# DE-130817_01.net
KiCad netlist of a schematic drawn in Altium Designer
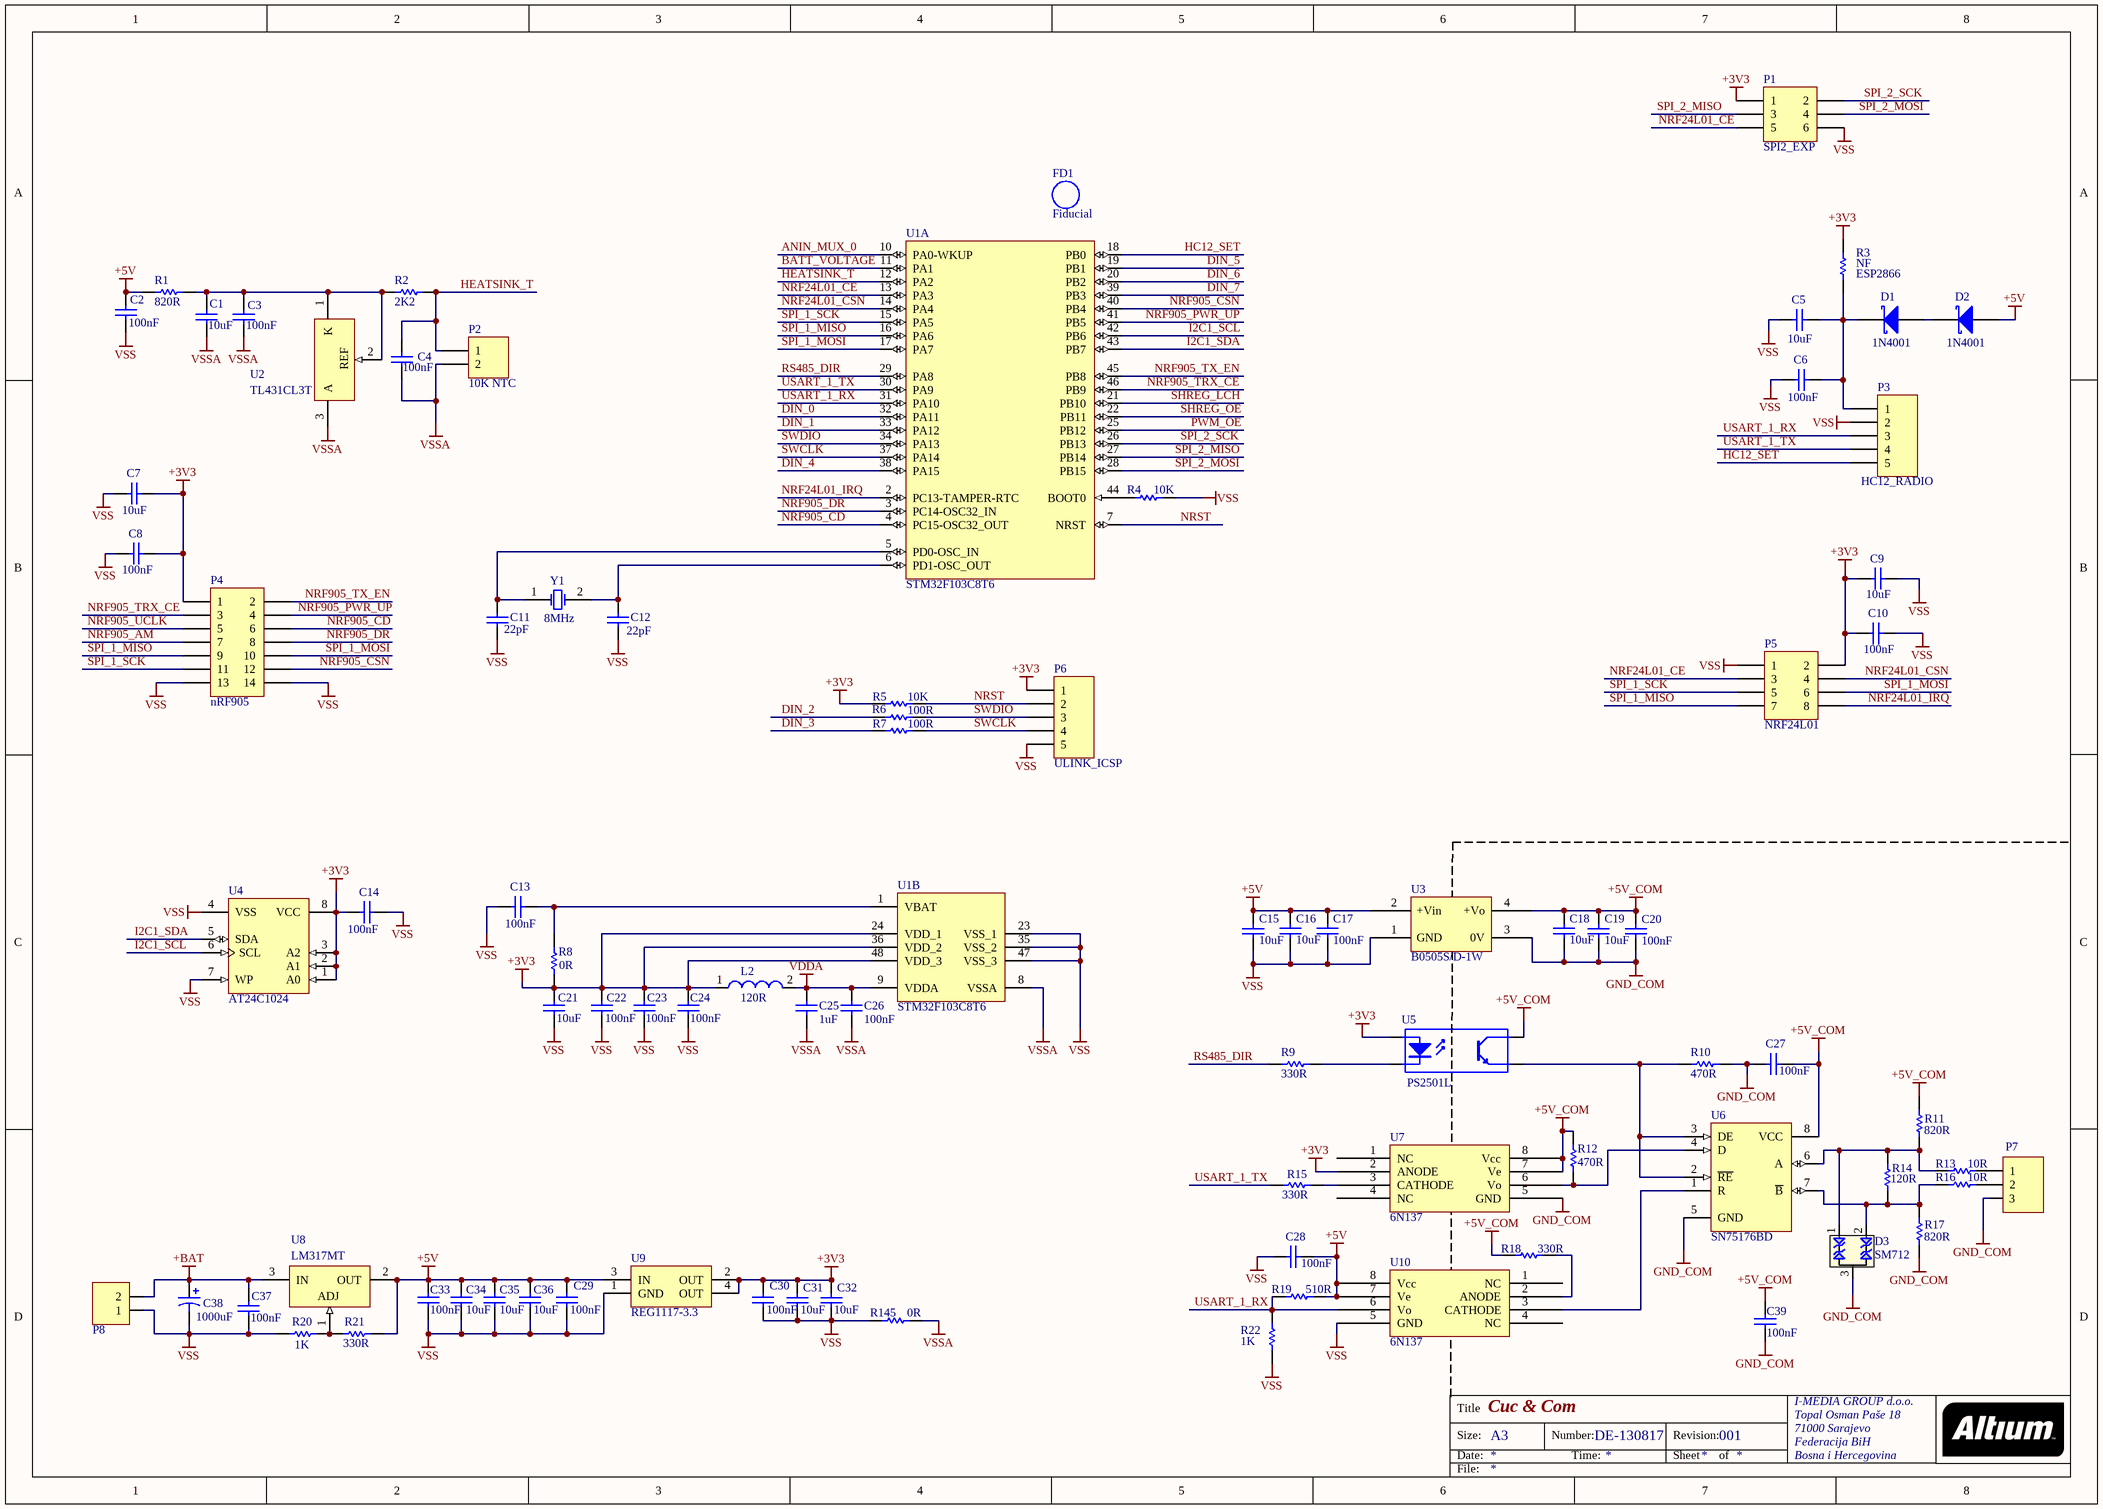
[diagram p0: DE-130817_01.SchDoc]

(export (version "E")
  (design (tool "Eeschema 10.0.6"))
  (components
    (comp (ref "C1")
      (value "10uF")
      (footprint "0805")
      (description "Ceramic Chip Capacitor - Standard")
      (fields (field (name "PUBLISHER") "Altium Limited"))
      (libsource (lib "KEMET Chip Capacitor") (part "C0805"))
    )
    (comp (ref "C2")
      (value "100nF")
      (footprint "0603")
      (description "Ceramic Chip Capacitor - Standard")
      (fields (field (name "PUBLISHER") "Altium Limited"))
      (libsource (lib "KEMET Chip Capacitor") (part "C0603"))
    )
    (comp (ref "C3")
      (value "100nF")
      (footprint "0603")
      (description "Ceramic Chip Capacitor - Standard")
      (fields (field (name "PUBLISHER") "Altium Limited"))
      (libsource (lib "KEMET Chip Capacitor") (part "C0603"))
    )
    (comp (ref "C4")
      (value "100nF")
      (footprint "0603")
      (description "Ceramic Chip Capacitor - Standard")
      (fields (field (name "PUBLISHER") "Altium Limited"))
      (libsource (lib "KEMET Chip Capacitor") (part "C0603"))
    )
    (comp (ref "C5")
      (value "10uF")
      (footprint "0805")
      (description "Ceramic Chip Capacitor - Standard")
      (fields (field (name "PUBLISHER") "Altium Limited"))
      (libsource (lib "KEMET Chip Capacitor") (part "C0805"))
    )
    (comp (ref "C6")
      (value "100nF")
      (footprint "0603")
      (description "Ceramic Chip Capacitor - Standard")
      (fields (field (name "PUBLISHER") "Altium Limited"))
      (libsource (lib "KEMET Chip Capacitor") (part "C0603"))
    )
    (comp (ref "C7")
      (value "10uF")
      (footprint "0805")
      (description "Ceramic Chip Capacitor - Standard")
      (fields (field (name "PUBLISHER") "Altium Limited"))
      (libsource (lib "KEMET Chip Capacitor") (part "C0805"))
    )
    (comp (ref "C8")
      (value "100nF")
      (footprint "0603")
      (description "Ceramic Chip Capacitor - Standard")
      (fields (field (name "PUBLISHER") "Altium Limited"))
      (libsource (lib "KEMET Chip Capacitor") (part "C0603"))
    )
    (comp (ref "C9")
      (value "10uF")
      (footprint "0805")
      (description "Ceramic Chip Capacitor - Standard")
      (fields (field (name "PUBLISHER") "Altium Limited"))
      (libsource (lib "KEMET Chip Capacitor") (part "C0805"))
    )
    (comp (ref "C10")
      (value "100nF")
      (footprint "0603")
      (description "Ceramic Chip Capacitor - Standard")
      (fields (field (name "PUBLISHER") "Altium Limited"))
      (libsource (lib "KEMET Chip Capacitor") (part "C0603"))
    )
    (comp (ref "C11")
      (value "22pF")
      (footprint "0603")
      (description "Ceramic Chip Capacitor - Standard")
      (fields (field (name "PUBLISHER") "Altium Limited"))
      (libsource (lib "KEMET Chip Capacitor") (part "C0603"))
    )
    (comp (ref "C12")
      (value "22pF")
      (footprint "0603")
      (description "Ceramic Chip Capacitor - Standard")
      (fields (field (name "PUBLISHER") "Altium Limited"))
      (libsource (lib "KEMET Chip Capacitor") (part "C0603"))
    )
    (comp (ref "C13")
      (value "100nF")
      (footprint "0603")
      (description "Ceramic Chip Capacitor - Standard")
      (fields (field (name "PUBLISHER") "Altium Limited"))
      (libsource (lib "KEMET Chip Capacitor") (part "C0603"))
    )
    (comp (ref "C14")
      (value "100nF")
      (footprint "0603")
      (description "Ceramic Chip Capacitor - Standard")
      (fields (field (name "PUBLISHER") "Altium Limited"))
      (libsource (lib "DE-251215") (part "C0603"))
    )
    (comp (ref "C15")
      (value "10uF")
      (footprint "0805")
      (description "Ceramic Chip Capacitor - Standard")
      (fields (field (name "PUBLISHER") "Altium Limited"))
      (libsource (lib "DE-110817") (part "C0805"))
    )
    (comp (ref "C16")
      (value "10uF")
      (footprint "0805")
      (description "Ceramic Chip Capacitor - Standard")
      (fields (field (name "PUBLISHER") "Altium Limited"))
      (libsource (lib "DE-110817") (part "C0805"))
    )
    (comp (ref "C17")
      (value "100nF")
      (footprint "0603")
      (description "Ceramic Chip Capacitor - Standard")
      (fields (field (name "PUBLISHER") "Altium Limited"))
      (libsource (lib "DE-110817") (part "C0603"))
    )
    (comp (ref "C18")
      (value "10uF")
      (footprint "0805")
      (description "Ceramic Chip Capacitor - Standard")
      (fields (field (name "PUBLISHER") "Altium Limited"))
      (libsource (lib "DE-110817") (part "C0805"))
    )
    (comp (ref "C19")
      (value "10uF")
      (footprint "0805")
      (description "Ceramic Chip Capacitor - Standard")
      (fields (field (name "PUBLISHER") "Altium Limited"))
      (libsource (lib "DE-110817") (part "C0805"))
    )
    (comp (ref "C20")
      (value "100nF")
      (footprint "0603")
      (description "Ceramic Chip Capacitor - Standard")
      (fields (field (name "PUBLISHER") "Altium Limited"))
      (libsource (lib "DE-110817") (part "C0603"))
    )
    (comp (ref "C21")
      (value "10uF")
      (footprint "0805")
      (description "Ceramic Chip Capacitor - Standard")
      (fields (field (name "PUBLISHER") "Altium Limited"))
      (libsource (lib "KEMET Chip Capacitor") (part "C0805"))
    )
    (comp (ref "C22")
      (value "100nF")
      (footprint "0603")
      (description "Ceramic Chip Capacitor - Standard")
      (fields (field (name "PUBLISHER") "Altium Limited"))
      (libsource (lib "KEMET Chip Capacitor") (part "C0603"))
    )
    (comp (ref "C23")
      (value "100nF")
      (footprint "0603")
      (description "Ceramic Chip Capacitor - Standard")
      (fields (field (name "PUBLISHER") "Altium Limited"))
      (libsource (lib "KEMET Chip Capacitor") (part "C0603"))
    )
    (comp (ref "C24")
      (value "100nF")
      (footprint "0603")
      (description "Ceramic Chip Capacitor - Standard")
      (fields (field (name "PUBLISHER") "Altium Limited"))
      (libsource (lib "KEMET Chip Capacitor") (part "C0603"))
    )
    (comp (ref "C25")
      (value "1uF")
      (footprint "0603")
      (description "Ceramic Chip Capacitor - Standard")
      (fields (field (name "PUBLISHER") "Altium Limited"))
      (libsource (lib "KEMET Chip Capacitor") (part "C0603"))
    )
    (comp (ref "C26")
      (value "100nF")
      (footprint "0603")
      (description "Ceramic Chip Capacitor - Standard")
      (fields (field (name "PUBLISHER") "Altium Limited"))
      (libsource (lib "KEMET Chip Capacitor") (part "C0603"))
    )
    (comp (ref "C27")
      (value "100nF")
      (footprint "0603")
      (description "Ceramic Chip Capacitor - Standard")
      (fields (field (name "PUBLISHER") "Altium Limited"))
      (libsource (lib "DE-251215") (part "C0603"))
    )
    (comp (ref "C28")
      (value "100nF")
      (footprint "0603")
      (description "Ceramic Chip Capacitor - Standard")
      (fields (field (name "PUBLISHER") "Altium Limited"))
      (libsource (lib "DE-251215") (part "C0603"))
    )
    (comp (ref "C29")
      (value "100nF")
      (footprint "0603")
      (description "Ceramic Chip Capacitor - Standard")
      (fields (field (name "PUBLISHER") "Altium Limited"))
      (libsource (lib "DE-251215") (part "C0603"))
    )
    (comp (ref "C30")
      (value "100nF")
      (footprint "0603")
      (description "Ceramic Chip Capacitor - Standard")
      (fields (field (name "PUBLISHER") "Altium Limited"))
      (libsource (lib "DE-251215") (part "C0603"))
    )
    (comp (ref "C31")
      (value "10uF")
      (footprint "0805")
      (description "Ceramic Chip Capacitor - Standard")
      (fields (field (name "PUBLISHER") "Altium Limited"))
      (libsource (lib "DE-251215") (part "C0805"))
    )
    (comp (ref "C32")
      (value "10uF")
      (footprint "0805")
      (description "Ceramic Chip Capacitor - Standard")
      (fields (field (name "PUBLISHER") "Altium Limited"))
      (libsource (lib "DE-251215") (part "C0805"))
    )
    (comp (ref "C33")
      (value "100nF")
      (footprint "0603")
      (description "Ceramic Chip Capacitor - Standard")
      (fields (field (name "PUBLISHER") "Altium Limited"))
      (libsource (lib "DE-251215") (part "C0603"))
    )
    (comp (ref "C34")
      (value "10uF")
      (footprint "0805")
      (description "Ceramic Chip Capacitor - Standard")
      (fields (field (name "PUBLISHER") "Altium Limited"))
      (libsource (lib "DE-251215") (part "C0805"))
    )
    (comp (ref "C35")
      (value "10uF")
      (footprint "0805")
      (description "Ceramic Chip Capacitor - Standard")
      (fields (field (name "PUBLISHER") "Altium Limited"))
      (libsource (lib "DE-251215") (part "C0805"))
    )
    (comp (ref "C36")
      (value "10uF")
      (footprint "0805")
      (description "Ceramic Chip Capacitor - Standard")
      (fields (field (name "PUBLISHER") "Altium Limited"))
      (libsource (lib "DE-200216_03") (part "C0805"))
    )
    (comp (ref "C37")
      (value "100nF")
      (footprint "0603")
      (description "Ceramic Chip Capacitor - Standard")
      (fields (field (name "PUBLISHER") "Altium Limited"))
      (libsource (lib "DE-251215") (part "C0603"))
    )
    (comp (ref "C38")
      (value "1000uF")
      (footprint "CAPPR5-10x16")
      (description "Aluminum Electrolytic Capacitor, Radial Style with Long Leads: 1000uF, 16V")
      (fields (field (name "PUBLISHER") "Altium Limited"))
      (libsource (lib "Vishay Roederstein Electrolytic Radial-Lead Capacitor") (part "EKA00DD410D00"))
    )
    (comp (ref "C39")
      (value "100nF")
      (footprint "0603")
      (description "Ceramic Chip Capacitor - Standard")
      (fields (field (name "PUBLISHER") "Altium Limited"))
      (libsource (lib "DE-251215") (part "C0603"))
    )
    (comp (ref "D1")
      (value "1N4001")
      (footprint "SMA")
      (description "Schottky Rectifier")
      (fields (field (name "PUBLISHER") "Altium Limited"))
      (libsource (lib "IR Rectifier - Schottky") (part "10MQ060N"))
    )
    (comp (ref "D2")
      (value "1N4001")
      (footprint "SMA")
      (description "Schottky Rectifier")
      (fields (field (name "PUBLISHER") "Altium Limited"))
      (libsource (lib "IR Rectifier - Schottky") (part "10MQ060N"))
    )
    (comp (ref "D3")
      (value "SM712")
      (footprint "SOT23_3L")
      (description "TVS Diode WE-TVS-Standard, VRWM=5.0V")
      (fields (field (name "PARTNUMBER") "824022"))
      (libsource (lib "WE-TVS TVS Diode-Standard Series") (part "824022"))
    )
    (comp (ref "FD1")
      (value "Fiducial")
      (footprint "Fiducial")
      (description "Fiduchial mark")
      (libsource (lib "DE-200216_02_1") (part "Fiduchial"))
    )
    (comp (ref "L2")
      (value "120R")
      (footprint "SMD-0805")
      (description "SMD EMI Suppression Ferrite Bead WE-CBF, Z = 120 Ohm")
      (fields (field (name "PARTNUMBER") "74279202"))
      (libsource (lib "WE-CBF SMD EMI Suppression Ferrite Bead") (part "74279202"))
    )
    (comp (ref "P1")
      (value "SPI2_EXP")
      (footprint "HDR2X3")
      (description "Header, 3-Pin, Dual row")
      (fields (field (name "PUBLISHER") "Altium Limited"))
      (libsource (lib "Miscellaneous Connectors") (part "Header 3X2"))
    )
    (comp (ref "P2")
      (value "10K NTC")
      (footprint "HDR1X2")
      (description "Header, 2-Pin")
      (fields (field (name "PUBLISHER") "Altium Limited"))
      (libsource (lib "Miscellaneous Connectors") (part "Header 2"))
    )
    (comp (ref "P3")
      (value "HC12_RADIO")
      (footprint "HDR1X5")
      (description "Header, 5-Pin")
      (fields (field (name "PUBLISHER") "Altium Limited"))
      (libsource (lib "Miscellaneous Connectors") (part "Header 5"))
    )
    (comp (ref "P4")
      (value "nRF905")
      (footprint "HDR2X7")
      (description "Header, 7-Pin, Dual row")
      (fields (field (name "PUBLISHER") "Altium Limited"))
      (libsource (lib "Miscellaneous Connectors") (part "Header 7X2"))
    )
    (comp (ref "P5")
      (value "NRF24L01")
      (footprint "HDR2X4")
      (description "Header, 4-Pin, Dual row")
      (fields (field (name "PUBLISHER") "Altium Limited"))
      (libsource (lib "Miscellaneous Connectors") (part "Header 4X2"))
    )
    (comp (ref "P6")
      (value "ULINK_ICSP")
      (footprint "HDR1X5")
      (description "Header, 5-Pin")
      (fields (field (name "PUBLISHER") "Altium Limited"))
      (libsource (lib "Miscellaneous Connectors") (part "Header 5"))
    )
    (comp (ref "P7")
      (value "TERMINAL BLOK 3")
      (footprint "TERMINAL BLOK 3")
      (description "3 pinski terminal blok konektor")
      (libsource (lib "DE-110817") (part "TERMINAL BLOK 3"))
    )
    (comp (ref "P8")
      (value "TERMINAL BLOK 2")
      (footprint "TERMINAL BLOK 2")
      (description "2 pinski terminal blok")
      (libsource (lib "DE-130817") (part "TERMINAL BLOK 2"))
    )
    (comp (ref "R1")
      (value "820R")
      (footprint "ERA-0603")
      (fields (field (name "PUBLISHER") "Altium Limited"))
      (libsource (lib "DE-200216_03") (part "ERAV"))
    )
    (comp (ref "R2")
      (value "2K2")
      (footprint "ERA-0603")
      (fields (field (name "PUBLISHER") "Altium Limited"))
      (libsource (lib "DE-200216_03") (part "ERAV"))
    )
    (comp (ref "R3")
      (value "NF")
      (footprint "ERA-0603")
      (fields (field (name "PUBLISHER") "Altium Limited"))
      (libsource (lib "DE-200216_03") (part "ERAV"))
    )
    (comp (ref "R4")
      (value "10K")
      (footprint "ERA-0603")
      (fields (field (name "PUBLISHER") "Altium Limited"))
      (libsource (lib "Panasonic Resistor") (part "ERA3Y"))
    )
    (comp (ref "R5")
      (value "10K")
      (footprint "ERA-0603")
      (fields (field (name "PUBLISHER") "Altium Limited"))
      (libsource (lib "Panasonic Resistor") (part "ERA3Y"))
    )
    (comp (ref "R6")
      (value "100R")
      (footprint "ERA-0603")
      (fields (field (name "PUBLISHER") "Altium Limited"))
      (libsource (lib "Panasonic Resistor") (part "ERA3Y"))
    )
    (comp (ref "R7")
      (value "100R")
      (footprint "ERA-0603")
      (fields (field (name "PUBLISHER") "Altium Limited"))
      (libsource (lib "Panasonic Resistor") (part "ERA3Y"))
    )
    (comp (ref "R8")
      (value "0R")
      (footprint "ERA-0603")
      (fields (field (name "PUBLISHER") "Altium Limited"))
      (libsource (lib "Panasonic Resistor") (part "ERA3Y"))
    )
    (comp (ref "R9")
      (value "330R")
      (footprint "ERA-0603")
      (fields (field (name "PUBLISHER") "Altium Limited"))
      (libsource (lib "DE-200216_01") (part "ERAV"))
    )
    (comp (ref "R10")
      (value "470R")
      (footprint "ERA-0603")
      (fields (field (name "PUBLISHER") "Altium Limited"))
      (libsource (lib "DE-200216_01") (part "ERAV"))
    )
    (comp (ref "R11")
      (value "820R")
      (footprint "ERA-0805")
      (fields (field (name "PUBLISHER") "Altium Limited"))
      (libsource (lib "Panasonic Resistor") (part "ERA6Y"))
    )
    (comp (ref "R12")
      (value "470R")
      (footprint "ERA-0603")
      (fields (field (name "PUBLISHER") "Altium Limited"))
      (libsource (lib "DE-200216_01") (part "ERAV"))
    )
    (comp (ref "R13")
      (value "10R")
      (footprint "ERA-0805")
      (fields (field (name "PUBLISHER") "Altium Limited"))
      (libsource (lib "Panasonic Resistor") (part "ERA6Y"))
    )
    (comp (ref "R14")
      (value "120R")
      (footprint "ERA-0805")
      (fields (field (name "PUBLISHER") "Altium Limited"))
      (libsource (lib "Panasonic Resistor") (part "ERA6Y"))
    )
    (comp (ref "R15")
      (value "330R")
      (footprint "ERA-0603")
      (fields (field (name "PUBLISHER") "Altium Limited"))
      (libsource (lib "Panasonic Resistor") (part "ERA3Y"))
    )
    (comp (ref "R16")
      (value "10R")
      (footprint "ERA-0805")
      (fields (field (name "PUBLISHER") "Altium Limited"))
      (libsource (lib "Panasonic Resistor") (part "ERA6Y"))
    )
    (comp (ref "R17")
      (value "820R")
      (footprint "ERA-0805")
      (fields (field (name "PUBLISHER") "Altium Limited"))
      (libsource (lib "Panasonic Resistor") (part "ERA6Y"))
    )
    (comp (ref "R18")
      (value "330R")
      (footprint "ERA-0603")
      (fields (field (name "PUBLISHER") "Altium Limited"))
      (libsource (lib "DE-200216_01") (part "ERAV"))
    )
    (comp (ref "R19")
      (value "510R")
      (footprint "ERA-0603")
      (fields (field (name "PUBLISHER") "Altium Limited"))
      (libsource (lib "DE-200216_01") (part "ERAV"))
    )
    (comp (ref "R20")
      (value "1K")
      (footprint "ERA-0805")
      (fields (field (name "PUBLISHER") "Altium Limited"))
      (libsource (lib "Panasonic Resistor") (part "ERA6Y"))
    )
    (comp (ref "R21")
      (value "330R")
      (footprint "ERA-0805")
      (fields (field (name "PUBLISHER") "Altium Limited"))
      (libsource (lib "Panasonic Resistor") (part "ERA6Y"))
    )
    (comp (ref "R22")
      (value "1K")
      (footprint "ERA-0603")
      (fields (field (name "PUBLISHER") "Altium Limited"))
      (libsource (lib "DE-200216_01") (part "ERAV"))
    )
    (comp (ref "R145")
      (value "0R")
      (footprint "ERA-0603")
      (fields (field (name "PUBLISHER") "Altium Limited"))
      (libsource (lib "DE-130817") (part "ERAV"))
    )
    (comp (ref "U1")
      (value "STM32F103C8T6")
      (footprint "STM-LQFP48_N")
      (libsource (lib "STMicroelectronics STM32 F1") (part "STM32F103C8T6"))
    )
    (comp (ref "U2")
      (value "TL431CL3T")
      (footprint "SOT23-3_N")
      (description "Programmable Voltage Reference, 2.5 to 36V, 3-Pin SOT23-3, Tape and Reel")
      (libsource (lib "STMicroelectronics Power Management Voltage Reference") (part "TL431CL3T"))
    )
    (comp (ref "U3")
      (value "B0505S/D-1W")
      (footprint "B0505S-1W")
      (description "1W isolated dc dc converter")
      (libsource (lib "DE-110817") (part "B0505S/D"))
    )
    (comp (ref "U4")
      (value "AT24C1024")
      (footprint "SOIC-SN8_N")
      (description "64Kbit, 400kHz, 1.7V, I2C Serial EEPROM, 8-Pin SOIC 150mil, Commercial Temperature")
      (fields (field (name "PUBLISHER") "Altium Limited"))
      (libsource (lib "Microchip Memory I2C Serial EEPROM") (part "24AA64/SN"))
    )
    (comp (ref "U5")
      (value "PS2501L")
      (footprint "SOP4")
      (description "4-Pin Phototransistor Optocoupler")
      (fields (field (name "PUBLISHER") "Altium Limited"))
      (libsource (lib "DE-200216_03") (part "PC817 optocoupler"))
    )
    (comp (ref "U6")
      (value "SN75176BD")
      (footprint "D008_L")
      (description "Differential Bus Transceiver")
      (fields (field (name "PUBLISHER") "Altium Limited"))
      (libsource (lib "DE-251215") (part "SN75176BD"))
    )
    (comp (ref "U7")
      (value "6N137")
      (footprint "SMD-8")
      (description "High CMR, High Speed TTL Compatibile Optocoupler")
      (libsource (lib "") (part "6N137_1"))
    )
    (comp (ref "U8")
      (value "LM317MT")
      (footprint "221A-06")
      (description "Three-Terminal Adjustable Output Positive Voltage Regulator")
      (fields (field (name "PUBLISHER") "Altium Limited"))
      (libsource (lib "ON Semi Power Mgt Voltage Regulator") (part "LM317MT"))
    )
    (comp (ref "U9")
      (value "REG1117-3.3")
      (footprint "ZZ311")
      (description "800mA and 1A Low Dropout Positive Regulator 2.85V, 3.3V, 5V, and Adjustable")
      (fields (field (name "PUBLISHER") "Altium Limited"))
      (libsource (lib "DE-251215") (part "REG1117-3.3"))
    )
    (comp (ref "U10")
      (value "6N137")
      (footprint "SMD-8")
      (description "High CMR, High Speed TTL Compatibile Optocoupler")
      (libsource (lib "DE-110817") (part "6N137"))
    )
    (comp (ref "Y1")
      (value "8MHz")
      (footprint "HC49/4H_SMX")
      (description "Surface Mount Quartz Crystal")
      (fields (field (name "PUBLISHER") "Altium Limited"))
      (libsource (lib "C-MAC Crystal Oscillator") (part "HC49/4H_SMX"))
    )
  )
  (nets
    (net (code "1") (name "+3V3") (class "Default")
      (node (ref "C10") (pin "1") (pinfunction "1_1") (pintype "passive"))
      (node (ref "C14") (pin "1") (pinfunction "1_1") (pintype "passive"))
      (node (ref "C21") (pin "2") (pinfunction "2_2") (pintype "passive"))
      (node (ref "C22") (pin "2") (pinfunction "2_2") (pintype "passive"))
      (node (ref "C23") (pin "2") (pinfunction "2_2") (pintype "passive"))
      (node (ref "C24") (pin "2") (pinfunction "2_2") (pintype "passive"))
      (node (ref "C30") (pin "2") (pinfunction "2_2") (pintype "passive"))
      (node (ref "C31") (pin "2") (pinfunction "2_2") (pintype "passive"))
      (node (ref "C32") (pin "2") (pinfunction "2_2") (pintype "passive"))
      (node (ref "C7") (pin "1") (pinfunction "1_1") (pintype "passive"))
      (node (ref "C8") (pin "1") (pinfunction "1_1") (pintype "passive"))
      (node (ref "C9") (pin "1") (pinfunction "1_1") (pintype "passive"))
      (node (ref "L2") (pin "1") (pinfunction "1_1") (pintype "passive"))
      (node (ref "P1") (pin "1") (pinfunction "1_1") (pintype "passive"))
      (node (ref "P4") (pin "1") (pinfunction "1_1") (pintype "passive"))
      (node (ref "P5") (pin "2") (pinfunction "2_2") (pintype "passive"))
      (node (ref "P6") (pin "1") (pinfunction "1_1") (pintype "passive"))
      (node (ref "R3") (pin "2") (pinfunction "2_2") (pintype "passive"))
      (node (ref "R5") (pin "2") (pinfunction "2_2") (pintype "passive"))
      (node (ref "R8") (pin "2") (pinfunction "2_2") (pintype "passive"))
      (node (ref "U1") (pin "24") (pinfunction "VDD_1_24") (pintype "power_in"))
      (node (ref "U1") (pin "36") (pinfunction "VDD_2_36") (pintype "power_in"))
      (node (ref "U1") (pin "48") (pinfunction "VDD_3_48") (pintype "power_in"))
      (node (ref "U4") (pin "1") (pinfunction "A0_1") (pintype "input"))
      (node (ref "U4") (pin "2") (pinfunction "A1_2") (pintype "input"))
      (node (ref "U4") (pin "3") (pinfunction "A2_3") (pintype "input"))
      (node (ref "U4") (pin "8") (pinfunction "VCC_8") (pintype "power_in"))
      (node (ref "U5") (pin "1") (pinfunction "A_1") (pintype "passive"))
      (node (ref "U7") (pin "2") (pinfunction "ANODE_2") (pintype "passive"))
      (node (ref "U9") (pin "2") (pinfunction "OUT_2") (pintype "power_in"))
      (node (ref "U9") (pin "4") (pinfunction "OUT_4") (pintype "power_in"))
    )
    (net (code "2") (name "+5V") (class "Default")
      (node (ref "C15") (pin "2") (pinfunction "2_2") (pintype "passive"))
      (node (ref "C16") (pin "2") (pinfunction "2_2") (pintype "passive"))
      (node (ref "C17") (pin "2") (pinfunction "2_2") (pintype "passive"))
      (node (ref "C2") (pin "2") (pinfunction "2_2") (pintype "passive"))
      (node (ref "C28") (pin "1") (pinfunction "1_1") (pintype "passive"))
      (node (ref "C29") (pin "2") (pinfunction "2_2") (pintype "passive"))
      (node (ref "C33") (pin "2") (pinfunction "2_2") (pintype "passive"))
      (node (ref "C34") (pin "2") (pinfunction "2_2") (pintype "passive"))
      (node (ref "C35") (pin "2") (pinfunction "2_2") (pintype "passive"))
      (node (ref "C36") (pin "2") (pinfunction "2_2") (pintype "passive"))
      (node (ref "D2") (pin "1") (pinfunction "A_1") (pintype "passive"))
      (node (ref "R1") (pin "2") (pinfunction "2_2") (pintype "passive"))
      (node (ref "R19") (pin "1") (pinfunction "1_1") (pintype "passive"))
      (node (ref "R21") (pin "1") (pinfunction "1_1") (pintype "passive"))
      (node (ref "U10") (pin "7") (pinfunction "Ve_7") (pintype "passive"))
      (node (ref "U10") (pin "8") (pinfunction "Vcc_8") (pintype "passive"))
      (node (ref "U3") (pin "2") (pinfunction "+Vin_2") (pintype "passive"))
      (node (ref "U8") (pin "2") (pinfunction "OUT_2") (pintype "power_in"))
      (node (ref "U9") (pin "3") (pinfunction "IN_3") (pintype "power_in"))
    )
    (net (code "3") (name "+5V_COM") (class "Default")
      (node (ref "C18") (pin "2") (pinfunction "2_2") (pintype "passive"))
      (node (ref "C19") (pin "2") (pinfunction "2_2") (pintype "passive"))
      (node (ref "C20") (pin "2") (pinfunction "2_2") (pintype "passive"))
      (node (ref "C27") (pin "2") (pinfunction "2_2") (pintype "passive"))
      (node (ref "C39") (pin "1") (pinfunction "1_1") (pintype "passive"))
      (node (ref "R11") (pin "2") (pinfunction "2_2") (pintype "passive"))
      (node (ref "R12") (pin "1") (pinfunction "1_1") (pintype "passive"))
      (node (ref "R18") (pin "2") (pinfunction "2_2") (pintype "passive"))
      (node (ref "U3") (pin "4") (pinfunction "+Vo_4") (pintype "passive"))
      (node (ref "U5") (pin "4") (pinfunction "C_4") (pintype "passive"))
      (node (ref "U6") (pin "8") (pinfunction "VCC_8") (pintype "power_in"))
      (node (ref "U7") (pin "7") (pinfunction "Ve_7") (pintype "passive"))
      (node (ref "U7") (pin "8") (pinfunction "Vcc_8") (pintype "passive"))
    )
    (net (code "4") (name "+BAT") (class "Default")
      (node (ref "C37") (pin "2") (pinfunction "2_2") (pintype "passive"))
      (node (ref "C38") (pin "1") (pinfunction "1_1") (pintype "passive"))
      (node (ref "P8") (pin "2") (pinfunction "2_2") (pintype "passive"))
      (node (ref "U8") (pin "3") (pinfunction "IN_3") (pintype "power_in"))
    )
    (net (code "5") (name "/ANIN_MUX_0") (class "Default")
      (node (ref "U1") (pin "10") (pinfunction "PA0-WKUP_10") (pintype "bidirectional"))
    )
    (net (code "6") (name "/BATT_VOLTAGE") (class "Default")
      (node (ref "U1") (pin "11") (pinfunction "PA1_11") (pintype "bidirectional"))
    )
    (net (code "7") (name "/DIN_0") (class "Default")
      (node (ref "U1") (pin "32") (pinfunction "PA11_32") (pintype "bidirectional"))
    )
    (net (code "8") (name "/DIN_1") (class "Default")
      (node (ref "U1") (pin "33") (pinfunction "PA12_33") (pintype "bidirectional"))
    )
    (net (code "9") (name "/DIN_2") (class "Default")
      (node (ref "R6") (pin "2") (pinfunction "2_2") (pintype "passive"))
    )
    (net (code "10") (name "/DIN_3") (class "Default")
      (node (ref "R7") (pin "2") (pinfunction "2_2") (pintype "passive"))
    )
    (net (code "11") (name "/DIN_4") (class "Default")
      (node (ref "U1") (pin "38") (pinfunction "PA15_38") (pintype "bidirectional"))
    )
    (net (code "12") (name "/DIN_5") (class "Default")
      (node (ref "U1") (pin "19") (pinfunction "PB1_19") (pintype "bidirectional"))
    )
    (net (code "13") (name "/DIN_6") (class "Default")
      (node (ref "U1") (pin "20") (pinfunction "PB2_20") (pintype "bidirectional"))
    )
    (net (code "14") (name "/DIN_7") (class "Default")
      (node (ref "U1") (pin "39") (pinfunction "PB3_39") (pintype "bidirectional"))
    )
    (net (code "15") (name "/HC12_SET") (class "Default")
      (node (ref "P3") (pin "5") (pinfunction "5_5") (pintype "passive"))
      (node (ref "U1") (pin "18") (pinfunction "PB0_18") (pintype "bidirectional"))
    )
    (net (code "16") (name "/HEATSINK_T") (class "Default")
      (node (ref "C4") (pin "2") (pinfunction "2_2") (pintype "passive"))
      (node (ref "P2") (pin "1") (pinfunction "1_1") (pintype "passive"))
      (node (ref "R2") (pin "1") (pinfunction "1_1") (pintype "passive"))
      (node (ref "U1") (pin "12") (pinfunction "PA2_12") (pintype "bidirectional"))
    )
    (net (code "17") (name "/I2C1_SCL") (class "Default")
      (node (ref "U1") (pin "42") (pinfunction "PB6_42") (pintype "bidirectional"))
      (node (ref "U4") (pin "6") (pinfunction "SCL_6") (pintype "input"))
    )
    (net (code "18") (name "/I2C1_SDA") (class "Default")
      (node (ref "U1") (pin "43") (pinfunction "PB7_43") (pintype "bidirectional"))
      (node (ref "U4") (pin "5") (pinfunction "SDA_5") (pintype "bidirectional"))
    )
    (net (code "19") (name "/NRF24L01_CE") (class "Default")
      (node (ref "P1") (pin "5") (pinfunction "5_5") (pintype "passive"))
      (node (ref "P5") (pin "3") (pinfunction "3_3") (pintype "passive"))
      (node (ref "U1") (pin "13") (pinfunction "PA3_13") (pintype "bidirectional"))
    )
    (net (code "20") (name "/NRF24L01_CSN") (class "Default")
      (node (ref "P5") (pin "4") (pinfunction "4_4") (pintype "passive"))
      (node (ref "U1") (pin "14") (pinfunction "PA4_14") (pintype "bidirectional"))
    )
    (net (code "21") (name "/NRF24L01_IRQ") (class "Default")
      (node (ref "P5") (pin "8") (pinfunction "8_8") (pintype "passive"))
      (node (ref "U1") (pin "2") (pinfunction "PC13-TAMPER-RTC_2") (pintype "bidirectional"))
    )
    (net (code "22") (name "/NRF905_AM") (class "Default")
      (node (ref "P4") (pin "7") (pinfunction "7_7") (pintype "passive"))
    )
    (net (code "23") (name "/NRF905_CD") (class "Default")
      (node (ref "P4") (pin "6") (pinfunction "6_6") (pintype "passive"))
      (node (ref "U1") (pin "4") (pinfunction "PC15-OSC32_OUT_4") (pintype "bidirectional"))
    )
    (net (code "24") (name "/NRF905_CSN") (class "Default")
      (node (ref "P4") (pin "12") (pinfunction "12_12") (pintype "passive"))
      (node (ref "U1") (pin "40") (pinfunction "PB4_40") (pintype "bidirectional"))
    )
    (net (code "25") (name "/NRF905_DR") (class "Default")
      (node (ref "P4") (pin "8") (pinfunction "8_8") (pintype "passive"))
      (node (ref "U1") (pin "3") (pinfunction "PC14-OSC32_IN_3") (pintype "bidirectional"))
    )
    (net (code "26") (name "/NRF905_PWR_UP") (class "Default")
      (node (ref "P4") (pin "4") (pinfunction "4_4") (pintype "passive"))
      (node (ref "U1") (pin "41") (pinfunction "PB5_41") (pintype "bidirectional"))
    )
    (net (code "27") (name "/NRF905_TRX_CE") (class "Default")
      (node (ref "P4") (pin "3") (pinfunction "3_3") (pintype "passive"))
      (node (ref "U1") (pin "46") (pinfunction "PB9_46") (pintype "bidirectional"))
    )
    (net (code "28") (name "/NRF905_TX_EN") (class "Default")
      (node (ref "P4") (pin "2") (pinfunction "2_2") (pintype "passive"))
      (node (ref "U1") (pin "45") (pinfunction "PB8_45") (pintype "bidirectional"))
    )
    (net (code "29") (name "/NRF905_UCLK") (class "Default")
      (node (ref "P4") (pin "5") (pinfunction "5_5") (pintype "passive"))
    )
    (net (code "30") (name "/NRST") (class "Default")
      (node (ref "P6") (pin "2") (pinfunction "2_2") (pintype "passive"))
      (node (ref "R5") (pin "1") (pinfunction "1_1") (pintype "passive"))
      (node (ref "U1") (pin "7") (pinfunction "NRST_7") (pintype "bidirectional"))
    )
    (net (code "31") (name "/PWM_OE") (class "Default")
      (node (ref "U1") (pin "25") (pinfunction "PB12_25") (pintype "bidirectional"))
    )
    (net (code "32") (name "/RS485_DIR") (class "Default")
      (node (ref "R9") (pin "2") (pinfunction "2_2") (pintype "passive"))
      (node (ref "U1") (pin "29") (pinfunction "PA8_29") (pintype "bidirectional"))
    )
    (net (code "33") (name "/SHREG_LCH") (class "Default")
      (node (ref "U1") (pin "21") (pinfunction "PB10_21") (pintype "bidirectional"))
    )
    (net (code "34") (name "/SHREG_OE") (class "Default")
      (node (ref "U1") (pin "22") (pinfunction "PB11_22") (pintype "bidirectional"))
    )
    (net (code "35") (name "/SPI_1_MISO") (class "Default")
      (node (ref "P4") (pin "9") (pinfunction "9_9") (pintype "passive"))
      (node (ref "P5") (pin "7") (pinfunction "7_7") (pintype "passive"))
      (node (ref "U1") (pin "16") (pinfunction "PA6_16") (pintype "bidirectional"))
    )
    (net (code "36") (name "/SPI_1_MOSI") (class "Default")
      (node (ref "P4") (pin "10") (pinfunction "10_10") (pintype "passive"))
      (node (ref "P5") (pin "6") (pinfunction "6_6") (pintype "passive"))
      (node (ref "U1") (pin "17") (pinfunction "PA7_17") (pintype "bidirectional"))
    )
    (net (code "37") (name "/SPI_1_SCK") (class "Default")
      (node (ref "P4") (pin "11") (pinfunction "11_11") (pintype "passive"))
      (node (ref "P5") (pin "5") (pinfunction "5_5") (pintype "passive"))
      (node (ref "U1") (pin "15") (pinfunction "PA5_15") (pintype "bidirectional"))
    )
    (net (code "38") (name "/SPI_2_MISO") (class "Default")
      (node (ref "P1") (pin "3") (pinfunction "3_3") (pintype "passive"))
      (node (ref "U1") (pin "27") (pinfunction "PB14_27") (pintype "bidirectional"))
    )
    (net (code "39") (name "/SPI_2_MOSI") (class "Default")
      (node (ref "P1") (pin "4") (pinfunction "4_4") (pintype "passive"))
      (node (ref "U1") (pin "28") (pinfunction "PB15_28") (pintype "bidirectional"))
    )
    (net (code "40") (name "/SPI_2_SCK") (class "Default")
      (node (ref "P1") (pin "2") (pinfunction "2_2") (pintype "passive"))
      (node (ref "U1") (pin "26") (pinfunction "PB13_26") (pintype "bidirectional"))
    )
    (net (code "41") (name "/SWCLK") (class "Default")
      (node (ref "P6") (pin "4") (pinfunction "4_4") (pintype "passive"))
      (node (ref "R7") (pin "1") (pinfunction "1_1") (pintype "passive"))
      (node (ref "U1") (pin "37") (pinfunction "PA14_37") (pintype "bidirectional"))
    )
    (net (code "42") (name "/SWDIO") (class "Default")
      (node (ref "P6") (pin "3") (pinfunction "3_3") (pintype "passive"))
      (node (ref "R6") (pin "1") (pinfunction "1_1") (pintype "passive"))
      (node (ref "U1") (pin "34") (pinfunction "PA13_34") (pintype "bidirectional"))
    )
    (net (code "43") (name "/USART_1_RX") (class "Default")
      (node (ref "P3") (pin "3") (pinfunction "3_3") (pintype "passive"))
      (node (ref "R19") (pin "2") (pinfunction "2_2") (pintype "passive"))
      (node (ref "R22") (pin "2") (pinfunction "2_2") (pintype "passive"))
      (node (ref "U1") (pin "31") (pinfunction "PA10_31") (pintype "bidirectional"))
      (node (ref "U10") (pin "6") (pinfunction "Vo_6") (pintype "passive"))
    )
    (net (code "44") (name "/USART_1_TX") (class "Default")
      (node (ref "P3") (pin "4") (pinfunction "4_4") (pintype "passive"))
      (node (ref "R15") (pin "1") (pinfunction "1_1") (pintype "passive"))
      (node (ref "U1") (pin "30") (pinfunction "PA9_30") (pintype "bidirectional"))
    )
    (net (code "45") (name "GND_COM") (class "Default")
      (node (ref "C18") (pin "1") (pinfunction "1_1") (pintype "passive"))
      (node (ref "C19") (pin "1") (pinfunction "1_1") (pintype "passive"))
      (node (ref "C20") (pin "1") (pinfunction "1_1") (pintype "passive"))
      (node (ref "C27") (pin "1") (pinfunction "1_1") (pintype "passive"))
      (node (ref "C39") (pin "2") (pinfunction "2_2") (pintype "passive"))
      (node (ref "D3") (pin "3") (pinfunction "GND_3") (pintype "passive"))
      (node (ref "P7") (pin "3") (pinfunction "3_3") (pintype "passive"))
      (node (ref "R10") (pin "2") (pinfunction "2_2") (pintype "passive"))
      (node (ref "R17") (pin "1") (pinfunction "1_1") (pintype "passive"))
      (node (ref "U3") (pin "3") (pinfunction "0V_3") (pintype "passive"))
      (node (ref "U6") (pin "5") (pinfunction "GND_5") (pintype "power_in"))
      (node (ref "U7") (pin "5") (pinfunction "GND_5") (pintype "passive"))
    )
    (net (code "46") (name "Net-(D1-A)") (class "Default")
      (node (ref "D1") (pin "1") (pinfunction "A_1") (pintype "passive"))
      (node (ref "D2") (pin "2") (pinfunction "K_2") (pintype "passive"))
    )
    (net (code "47") (name "Net-(D1-K)") (class "Default")
      (node (ref "C5") (pin "1") (pinfunction "1_1") (pintype "passive"))
      (node (ref "C6") (pin "1") (pinfunction "1_1") (pintype "passive"))
      (node (ref "D1") (pin "2") (pinfunction "K_2") (pintype "passive"))
      (node (ref "P3") (pin "1") (pinfunction "1_1") (pintype "passive"))
      (node (ref "R3") (pin "1") (pinfunction "1_1") (pintype "passive"))
    )
    (net (code "48") (name "Net-(P7-Pad1)") (class "Default")
      (node (ref "P7") (pin "1") (pinfunction "1_1") (pintype "passive"))
      (node (ref "R13") (pin "2") (pinfunction "2_2") (pintype "passive"))
    )
    (net (code "49") (name "Net-(P7-Pad2)") (class "Default")
      (node (ref "P7") (pin "2") (pinfunction "2_2") (pintype "passive"))
      (node (ref "R16") (pin "2") (pinfunction "2_2") (pintype "passive"))
    )
    (net (code "50") (name "Net-(U1A-BOOT0)") (class "Default")
      (node (ref "R4") (pin "1") (pinfunction "1_1") (pintype "passive"))
      (node (ref "U1") (pin "44") (pinfunction "BOOT0_44") (pintype "input"))
    )
    (net (code "51") (name "Net-(U1A-PD0-OSC_IN)") (class "Default")
      (node (ref "C11") (pin "2") (pinfunction "2_2") (pintype "passive"))
      (node (ref "U1") (pin "5") (pinfunction "PD0-OSC_IN_5") (pintype "bidirectional"))
      (node (ref "Y1") (pin "1") (pinfunction "OSC1_1") (pintype "passive"))
    )
    (net (code "52") (name "Net-(U1A-PD1-OSC_OUT)") (class "Default")
      (node (ref "C12") (pin "2") (pinfunction "2_2") (pintype "passive"))
      (node (ref "U1") (pin "6") (pinfunction "PD1-OSC_OUT_6") (pintype "bidirectional"))
      (node (ref "Y1") (pin "2") (pinfunction "OSC2_2") (pintype "passive"))
    )
    (net (code "53") (name "Net-(U1B-VBAT)") (class "Default")
      (node (ref "C13") (pin "1") (pinfunction "1_1") (pintype "passive"))
      (node (ref "R8") (pin "1") (pinfunction "1_1") (pintype "passive"))
      (node (ref "U1") (pin "1") (pinfunction "VBAT_1") (pintype "power_in"))
    )
    (net (code "54") (name "Net-(U2-K)") (class "Default")
      (node (ref "C1") (pin "2") (pinfunction "2_2") (pintype "passive"))
      (node (ref "C3") (pin "2") (pinfunction "2_2") (pintype "passive"))
      (node (ref "R1") (pin "1") (pinfunction "1_1") (pintype "passive"))
      (node (ref "R2") (pin "2") (pinfunction "2_2") (pintype "passive"))
      (node (ref "U2") (pin "1") (pinfunction "K_1") (pintype "passive"))
      (node (ref "U2") (pin "2") (pinfunction "REF_2") (pintype "input"))
    )
    (net (code "55") (name "Net-(U5-E)") (class "Default")
      (node (ref "R10") (pin "1") (pinfunction "1_1") (pintype "passive"))
      (node (ref "U5") (pin "3") (pinfunction "E_3") (pintype "passive"))
      (node (ref "U6") (pin "2") (pinfunction "~{RE}_2") (pintype "input"))
      (node (ref "U6") (pin "3") (pinfunction "DE_3") (pintype "input"))
    )
    (net (code "56") (name "Net-(U5-K)") (class "Default")
      (node (ref "R9") (pin "1") (pinfunction "1_1") (pintype "passive"))
      (node (ref "U5") (pin "2") (pinfunction "K_2") (pintype "passive"))
    )
    (net (code "57") (name "Net-(U6-A)") (class "Default")
      (node (ref "D3") (pin "1") (pinfunction "I/O_1") (pintype "passive"))
      (node (ref "R11") (pin "1") (pinfunction "1_1") (pintype "passive"))
      (node (ref "R13") (pin "1") (pinfunction "1_1") (pintype "passive"))
      (node (ref "R14") (pin "2") (pinfunction "2_2") (pintype "passive"))
      (node (ref "U6") (pin "6") (pinfunction "A_6") (pintype "bidirectional"))
    )
    (net (code "58") (name "Net-(U6-D)") (class "Default")
      (node (ref "R12") (pin "2") (pinfunction "2_2") (pintype "passive"))
      (node (ref "U6") (pin "4") (pinfunction "D_4") (pintype "input"))
      (node (ref "U7") (pin "6") (pinfunction "Vo_6") (pintype "passive"))
    )
    (net (code "59") (name "Net-(U6-~{B})") (class "Default")
      (node (ref "D3") (pin "2") (pinfunction "I/O_2") (pintype "passive"))
      (node (ref "R14") (pin "1") (pinfunction "1_1") (pintype "passive"))
      (node (ref "R16") (pin "1") (pinfunction "1_1") (pintype "passive"))
      (node (ref "R17") (pin "2") (pinfunction "2_2") (pintype "passive"))
      (node (ref "U6") (pin "7") (pinfunction "~{B}_7") (pintype "bidirectional"))
    )
    (net (code "60") (name "Net-(U7-CATHODE)") (class "Default")
      (node (ref "R15") (pin "2") (pinfunction "2_2") (pintype "passive"))
      (node (ref "U7") (pin "3") (pinfunction "CATHODE_3") (pintype "passive"))
    )
    (net (code "61") (name "Net-(U8-ADJ)") (class "Default")
      (node (ref "R20") (pin "1") (pinfunction "1_1") (pintype "passive"))
      (node (ref "R21") (pin "2") (pinfunction "2_2") (pintype "passive"))
      (node (ref "U8") (pin "1") (pinfunction "ADJ_1") (pintype "input"))
    )
    (net (code "62") (name "Net-(U10-ANODE)") (class "Default")
      (node (ref "R18") (pin "1") (pinfunction "1_1") (pintype "passive"))
      (node (ref "U10") (pin "2") (pinfunction "ANODE_2") (pintype "passive"))
    )
    (net (code "63") (name "Net-(U10-CATHODE)") (class "Default")
      (node (ref "U10") (pin "3") (pinfunction "CATHODE_3") (pintype "passive"))
      (node (ref "U6") (pin "1") (pinfunction "R_1") (pintype "tri_state"))
    )
    (net (code "64") (name "VDDA") (class "Default")
      (node (ref "C25") (pin "2") (pinfunction "2_2") (pintype "passive"))
      (node (ref "C26") (pin "2") (pinfunction "2_2") (pintype "passive"))
      (node (ref "L2") (pin "2") (pinfunction "2_2") (pintype "passive"))
      (node (ref "U1") (pin "9") (pinfunction "VDDA_9") (pintype "power_in"))
    )
    (net (code "65") (name "VSS") (class "Default")
      (node (ref "C10") (pin "2") (pinfunction "2_2") (pintype "passive"))
      (node (ref "C11") (pin "1") (pinfunction "1_1") (pintype "passive"))
      (node (ref "C12") (pin "1") (pinfunction "1_1") (pintype "passive"))
      (node (ref "C13") (pin "2") (pinfunction "2_2") (pintype "passive"))
      (node (ref "C14") (pin "2") (pinfunction "2_2") (pintype "passive"))
      (node (ref "C15") (pin "1") (pinfunction "1_1") (pintype "passive"))
      (node (ref "C16") (pin "1") (pinfunction "1_1") (pintype "passive"))
      (node (ref "C17") (pin "1") (pinfunction "1_1") (pintype "passive"))
      (node (ref "C2") (pin "1") (pinfunction "1_1") (pintype "passive"))
      (node (ref "C21") (pin "1") (pinfunction "1_1") (pintype "passive"))
      (node (ref "C22") (pin "1") (pinfunction "1_1") (pintype "passive"))
      (node (ref "C23") (pin "1") (pinfunction "1_1") (pintype "passive"))
      (node (ref "C24") (pin "1") (pinfunction "1_1") (pintype "passive"))
      (node (ref "C28") (pin "2") (pinfunction "2_2") (pintype "passive"))
      (node (ref "C29") (pin "1") (pinfunction "1_1") (pintype "passive"))
      (node (ref "C30") (pin "1") (pinfunction "1_1") (pintype "passive"))
      (node (ref "C31") (pin "1") (pinfunction "1_1") (pintype "passive"))
      (node (ref "C32") (pin "1") (pinfunction "1_1") (pintype "passive"))
      (node (ref "C33") (pin "1") (pinfunction "1_1") (pintype "passive"))
      (node (ref "C34") (pin "1") (pinfunction "1_1") (pintype "passive"))
      (node (ref "C35") (pin "1") (pinfunction "1_1") (pintype "passive"))
      (node (ref "C36") (pin "1") (pinfunction "1_1") (pintype "passive"))
      (node (ref "C37") (pin "1") (pinfunction "1_1") (pintype "passive"))
      (node (ref "C38") (pin "2") (pinfunction "2_2") (pintype "passive"))
      (node (ref "C5") (pin "2") (pinfunction "2_2") (pintype "passive"))
      (node (ref "C6") (pin "2") (pinfunction "2_2") (pintype "passive"))
      (node (ref "C7") (pin "2") (pinfunction "2_2") (pintype "passive"))
      (node (ref "C8") (pin "2") (pinfunction "2_2") (pintype "passive"))
      (node (ref "C9") (pin "2") (pinfunction "2_2") (pintype "passive"))
      (node (ref "P1") (pin "6") (pinfunction "6_6") (pintype "passive"))
      (node (ref "P3") (pin "2") (pinfunction "2_2") (pintype "passive"))
      (node (ref "P4") (pin "13") (pinfunction "13_13") (pintype "passive"))
      (node (ref "P4") (pin "14") (pinfunction "14_14") (pintype "passive"))
      (node (ref "P5") (pin "1") (pinfunction "1_1") (pintype "passive"))
      (node (ref "P6") (pin "5") (pinfunction "5_5") (pintype "passive"))
      (node (ref "P8") (pin "1") (pinfunction "1_1") (pintype "passive"))
      (node (ref "R145") (pin "1") (pinfunction "1_1") (pintype "passive"))
      (node (ref "R20") (pin "2") (pinfunction "2_2") (pintype "passive"))
      (node (ref "R22") (pin "1") (pinfunction "1_1") (pintype "passive"))
      (node (ref "R4") (pin "2") (pinfunction "2_2") (pintype "passive"))
      (node (ref "U1") (pin "23") (pinfunction "VSS_1_23") (pintype "power_in"))
      (node (ref "U1") (pin "35") (pinfunction "VSS_2_35") (pintype "power_in"))
      (node (ref "U1") (pin "47") (pinfunction "VSS_3_47") (pintype "power_in"))
      (node (ref "U10") (pin "5") (pinfunction "GND_5") (pintype "passive"))
      (node (ref "U3") (pin "1") (pinfunction "GND_1") (pintype "passive"))
      (node (ref "U4") (pin "4") (pinfunction "VSS_4") (pintype "power_in"))
      (node (ref "U4") (pin "7") (pinfunction "WP_7") (pintype "input"))
      (node (ref "U9") (pin "1") (pinfunction "GND_1") (pintype "power_in"))
    )
    (net (code "66") (name "VSSA") (class "Default")
      (node (ref "C1") (pin "1") (pinfunction "1_1") (pintype "passive"))
      (node (ref "C25") (pin "1") (pinfunction "1_1") (pintype "passive"))
      (node (ref "C26") (pin "1") (pinfunction "1_1") (pintype "passive"))
      (node (ref "C3") (pin "1") (pinfunction "1_1") (pintype "passive"))
      (node (ref "C4") (pin "1") (pinfunction "1_1") (pintype "passive"))
      (node (ref "P2") (pin "2") (pinfunction "2_2") (pintype "passive"))
      (node (ref "R145") (pin "2") (pinfunction "2_2") (pintype "passive"))
      (node (ref "U1") (pin "8") (pinfunction "VSSA_8") (pintype "power_in"))
      (node (ref "U2") (pin "3") (pinfunction "A_3") (pintype "passive"))
    )
    (net (code "67") (name "unconnected-(U7-NC-Pad1)") (class "Default")
      (node (ref "U7") (pin "1") (pinfunction "NC_1") (pintype "passive"))
    )
    (net (code "68") (name "unconnected-(U7-NC-Pad4)") (class "Default")
      (node (ref "U7") (pin "4") (pinfunction "NC_4") (pintype "passive"))
    )
    (net (code "69") (name "unconnected-(U10-NC-Pad1)") (class "Default")
      (node (ref "U10") (pin "1") (pinfunction "NC_1") (pintype "passive"))
    )
    (net (code "70") (name "unconnected-(U10-NC-Pad4)") (class "Default")
      (node (ref "U10") (pin "4") (pinfunction "NC_4") (pintype "passive"))
    )
  )
)
